# F4x1_Dev.net
KiCad netlist of a schematic drawn in Altium Designer
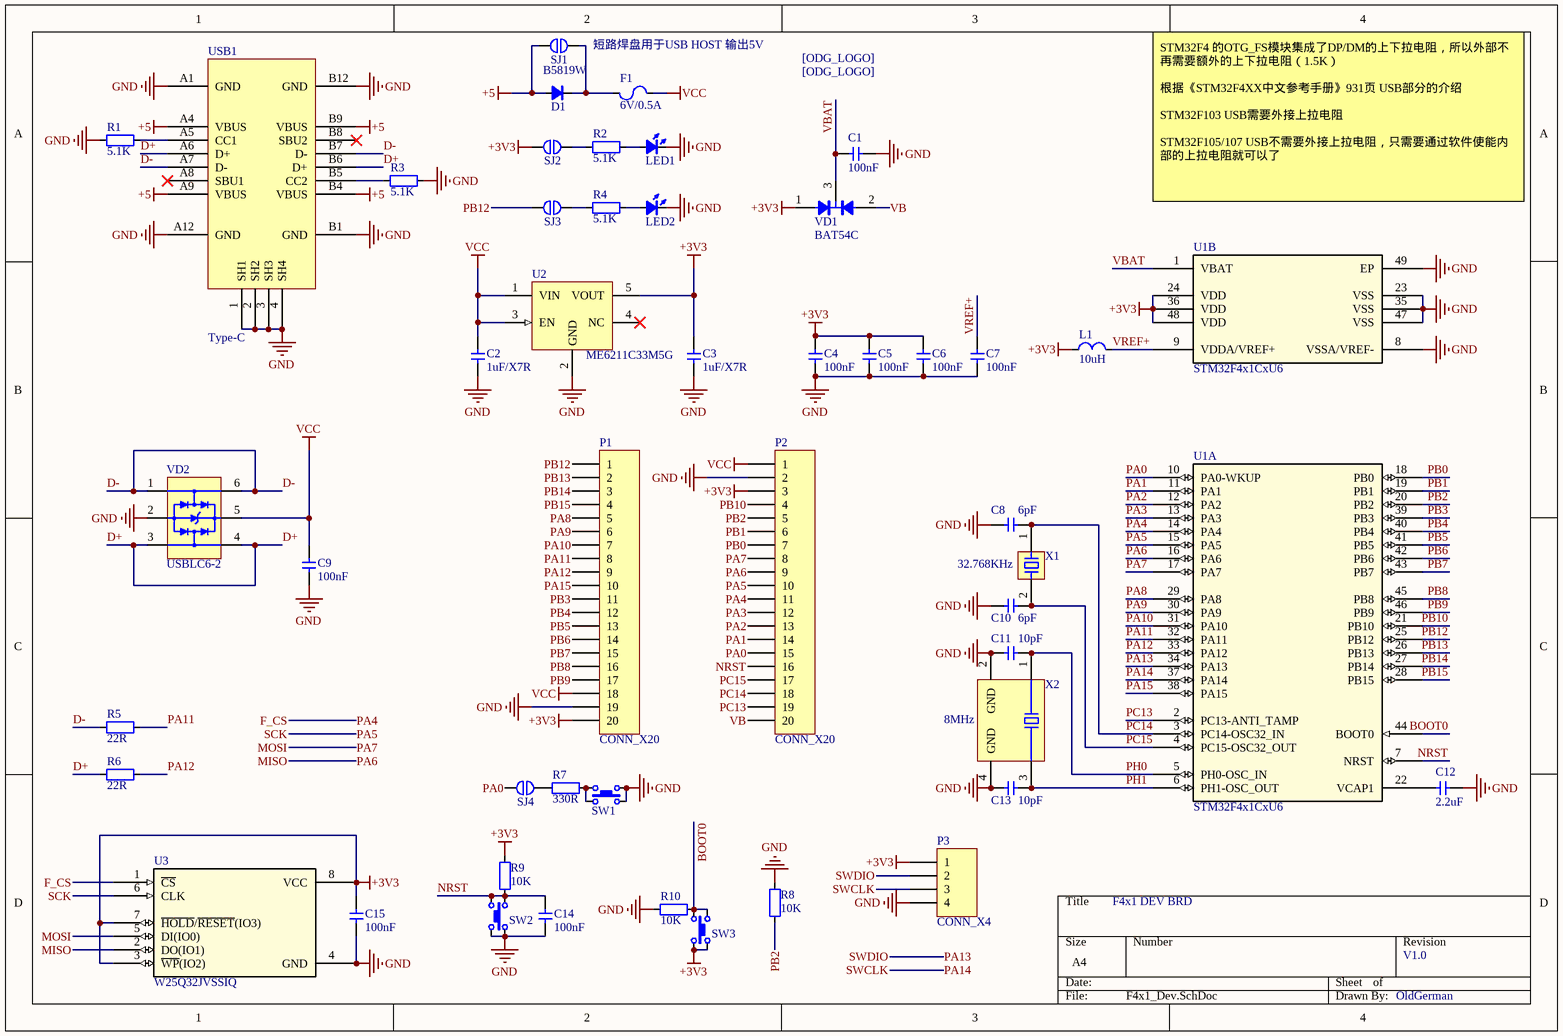
[diagram p0: F4x1_Dev.SchDoc]

(export (version "E")
  (design (tool "Eeschema 10.0.6"))
  (components
    (comp (ref "*1")
      (value "ODG_LOGO")
      (footprint "ODG_LOGO")
      (libsource (lib "ODG_AD_Lib") (part "ODG_LOGO"))
    )
    (comp (ref "*2")
      (value "ODG_LOGO")
      (footprint "ODG_LOGO")
      (libsource (lib "ODG_AD_Lib") (part "ODG_LOGO"))
    )
    (comp (ref "C1")
      (value "100nF")
      (footprint "C0603")
      (description "Capacitor")
      (libsource (lib "ODG_AD_Lib") (part "CAP"))
    )
    (comp (ref "C2")
      (value "1uF/X7R")
      (footprint "C0603")
      (description "Capacitor")
      (libsource (lib "ODG_AD_Lib") (part "CAP"))
    )
    (comp (ref "C3")
      (value "1uF/X7R")
      (footprint "C0603")
      (description "Capacitor")
      (libsource (lib "ODG_AD_Lib") (part "CAP"))
    )
    (comp (ref "C4")
      (value "100nF")
      (footprint "C0603")
      (description "Capacitor")
      (libsource (lib "ODG_AD_Lib") (part "CAP"))
    )
    (comp (ref "C5")
      (value "100nF")
      (footprint "C0603")
      (description "Capacitor")
      (libsource (lib "ODG_AD_Lib") (part "CAP"))
    )
    (comp (ref "C6")
      (value "100nF")
      (footprint "C0603")
      (description "Capacitor")
      (libsource (lib "ODG_AD_Lib") (part "CAP"))
    )
    (comp (ref "C7")
      (value "100nF")
      (footprint "C0603")
      (description "Capacitor")
      (libsource (lib "ODG_AD_Lib") (part "CAP"))
    )
    (comp (ref "C8")
      (value "6pF")
      (footprint "C0603")
      (description "Capacitor")
      (libsource (lib "ODG_AD_Lib") (part "CAP"))
    )
    (comp (ref "C9")
      (value "100nF")
      (footprint "C0603")
      (description "Capacitor")
      (libsource (lib "ODG_AD_Lib") (part "CAP"))
    )
    (comp (ref "C10")
      (value "6pF")
      (footprint "C0603")
      (description "Capacitor")
      (libsource (lib "ODG_AD_Lib") (part "CAP"))
    )
    (comp (ref "C11")
      (value "10pF")
      (footprint "C0603")
      (description "Capacitor")
      (libsource (lib "ODG_AD_Lib") (part "CAP"))
    )
    (comp (ref "C12")
      (value "2.2uF")
      (footprint "C0603")
      (description "Capacitor")
      (libsource (lib "ODG_AD_Lib") (part "CAP"))
    )
    (comp (ref "C13")
      (value "10pF")
      (footprint "C0603")
      (description "Capacitor")
      (libsource (lib "ODG_AD_Lib") (part "CAP"))
    )
    (comp (ref "C14")
      (value "100nF")
      (footprint "C0603")
      (description "Capacitor")
      (libsource (lib "ODG_AD_Lib") (part "CAP"))
    )
    (comp (ref "C15")
      (value "100nF")
      (footprint "C0603")
      (description "Capacitor")
      (libsource (lib "ODG_AD_Lib") (part "CAP"))
    )
    (comp (ref "D1")
      (value "B5819W")
      (footprint "SOD-323")
      (description "二极管")
      (libsource (lib "ODG_AD_Lib") (part "DIODE"))
    )
    (comp (ref "F1")
      (value "6V/0.5A")
      (footprint "FUSE0603_0.5MM")
      (description "贴片自恢复保险丝")
      (libsource (lib "ODG_AD_Lib") (part "FUSE"))
    )
    (comp (ref "L1")
      (value "10uH")
      (footprint "FER0603")
      (description "贴片叠层电感")
      (libsource (lib "ODG_AD_Lib") (part "inductor_mini"))
    )
    (comp (ref "LED1") (value "LED") (footprint "LED0603_GREEN") (libsource (lib "ODG_AD_Lib") (part "LED")))
    (comp (ref "LED2") (value "LED") (footprint "LED0603_YELLOW") (libsource (lib "ODG_AD_Lib") (part "LED")))
    (comp (ref "P1")
      (value "CONN_X20")
      (footprint "2.54MM_MALE_X20")
      (libsource (lib "ODG_AD_Lib") (part "CONN_X20"))
    )
    (comp (ref "P2")
      (value "CONN_X20")
      (footprint "2.54MM_MALE_X20")
      (libsource (lib "ODG_AD_Lib") (part "CONN_X20"))
    )
    (comp (ref "P3")
      (value "CONN_X4")
      (footprint "2.54mm_Male_x4")
      (libsource (lib "ODG_AD_Lib") (part "CONN_X4"))
    )
    (comp (ref "R1")
      (value "5.1K")
      (footprint "R0603")
      (description "Resistor")
      (libsource (lib "") (part "RES_1"))
    )
    (comp (ref "R2")
      (value "5.1K")
      (footprint "R0603")
      (description "Resistor")
      (libsource (lib "") (part "RES_1"))
    )
    (comp (ref "R3")
      (value "5.1K")
      (footprint "R0603")
      (description "Resistor")
      (libsource (lib "") (part "RES_1"))
    )
    (comp (ref "R4")
      (value "5.1K")
      (footprint "R0603")
      (description "Resistor")
      (libsource (lib "") (part "RES_1"))
    )
    (comp (ref "R5")
      (value "22R")
      (footprint "R0603")
      (description "Resistor")
      (libsource (lib "") (part "RES_1"))
    )
    (comp (ref "R6")
      (value "22R")
      (footprint "R0603")
      (description "Resistor")
      (libsource (lib "") (part "RES_1"))
    )
    (comp (ref "R7")
      (value "330R")
      (footprint "R0603")
      (description "Resistor")
      (libsource (lib "ODG_AD_Lib") (part "RES"))
    )
    (comp (ref "R8")
      (value "10K")
      (footprint "R0603")
      (description "Resistor")
      (libsource (lib "") (part "RES_2"))
    )
    (comp (ref "R9")
      (value "10K")
      (footprint "R0603")
      (description "Resistor")
      (libsource (lib "") (part "RES_3"))
    )
    (comp (ref "R10")
      (value "10K")
      (footprint "R0603")
      (description "Resistor")
      (libsource (lib "ODG_AD_Lib") (part "RES"))
    )
    (comp (ref "SJ1")
      (value "SJ_2P")
      (footprint "SJ_2P")
      (description "焊接跳线")
      (libsource (lib "ODG_AD_Lib") (part "SJ_2P"))
    )
    (comp (ref "SJ2")
      (value "SJ_2P")
      (footprint "SJ_2P_MINI")
      (description "焊接跳线")
      (libsource (lib "ODG_AD_Lib") (part "SJ_2P"))
    )
    (comp (ref "SJ3")
      (value "SJ_2P")
      (footprint "SJ_2P_MINI")
      (description "焊接跳线")
      (libsource (lib "ODG_AD_Lib") (part "SJ_2P"))
    )
    (comp (ref "SJ4")
      (value "SJ_2P")
      (footprint "SJ_2P_MINI")
      (description "焊接跳线")
      (libsource (lib "ODG_AD_Lib") (part "SJ_2P"))
    )
    (comp (ref "SW1")
      (value "Button-4P")
      (footprint "SWITCH_3X4X2.5_4PIN_SMD")
      (description "Button")
      (libsource (lib "ODG_AD_Lib") (part "Button-4P"))
    )
    (comp (ref "SW2")
      (value "Button-4P")
      (footprint "SWITCH_3X4X2.5_4PIN_SMD")
      (description "Button")
      (libsource (lib "ODG_AD_Lib") (part "Button-4P"))
    )
    (comp (ref "SW3")
      (value "Button-4P")
      (footprint "SWITCH_3X4X2.5_4PIN_SMD")
      (description "Button")
      (libsource (lib "ODG_AD_Lib") (part "Button-4P"))
    )
    (comp (ref "U1")
      (value "STM32F4x1CxU6")
      (footprint "UFQFPN-48_7X7X0P55MM_VIA")
      (description "No Description Available")
      (fields
        (field (name "MANUFACTURER_PART_NUMBER") "STM32F411CEU7")
        (field (name "COPYRIGHT") "Copyright (C) 2022 Ultra Librarian. All rights reserved.")
      )
      (libsource (lib "ODG_AD_Lib") (part "STM32F411CEU7"))
    )
    (comp (ref "U2")
      (value "ME6211C33M5G")
      (footprint "ANALOG TSOT-23-5 UJ-5")
      (description "线性稳压芯片")
      (fields (field (name "版权归属") "源创客"))
      (libsource (lib "ODG_AD_Lib") (part "ME6211C33M5G"))
    )
    (comp (ref "U3")
      (value "W25Q32JVSSIQ")
      (footprint "WIN_SS-8_WIN-L")
      (description "No Description Available")
      (fields
        (field (name "MANUFACTURER_PART_NUMBER") "W25Q16DVSSIG")
        (field (name "COPYRIGHT") "Copyright (C) 2022 Ultra Librarian. All rights reserved.")
      )
      (libsource (lib "ODG_AD_Lib") (part "W25Qxx"))
    )
    (comp (ref "USB1")
      (value "Type-C")
      (footprint "Type-C-TOP")
      (libsource (lib "ODG_AD_Lib") (part "USB-Type-C_16P"))
    )
    (comp (ref "VD1")
      (value "BAT54C")
      (footprint "ON SEMI SOT-23-3")
      (description "贴片肖特基二极管")
      (fields (field (name "版权归属") "源创客"))
      (libsource (lib "ODG_AD_Lib") (part "BAT54C"))
    )
    (comp (ref "VD2")
      (value "USBLC6-2")
      (footprint "MICROCHIP SOT-23-6 M6")
      (fields (field (name "版权归属") "源创客"))
      (libsource (lib "ODG_AD_Lib") (part "USBLC6-2"))
    )
    (comp (ref "X1")
      (value "32.768KHz")
      (footprint "XTAL_2P_3215")
      (description "2脚无源石英晶振")
      (fields (field (name "版权归属") "源创客"))
      (libsource (lib "ODG_AD_Lib") (part "XTAL-2P"))
    )
    (comp (ref "X2")
      (value "8MHz")
      (footprint "EPSON TSX-3225")
      (description "4脚无源石英晶振")
      (fields (field (name "版权归属") "源创客"))
      (libsource (lib "ODG_AD_Lib") (part "XTAL-4P"))
    )
  )
  (nets
    (net (code "1") (name "+3V3") (class "Default")
      (node (ref "C15") (pin "2") (pinfunction "2_2") (pintype "passive"))
      (node (ref "C3") (pin "2") (pinfunction "2_2") (pintype "passive"))
      (node (ref "C4") (pin "2") (pinfunction "2_2") (pintype "passive"))
      (node (ref "C5") (pin "1") (pinfunction "1_1") (pintype "passive"))
      (node (ref "C6") (pin "1") (pinfunction "1_1") (pintype "passive"))
      (node (ref "L1") (pin "1") (pinfunction "1_1") (pintype "passive"))
      (node (ref "P1") (pin "20") (pinfunction "20_20") (pintype "passive"))
      (node (ref "P2") (pin "3") (pinfunction "3_3") (pintype "passive"))
      (node (ref "P3") (pin "1") (pinfunction "1_1") (pintype "passive"))
      (node (ref "R9") (pin "1") (pinfunction "1_1") (pintype "passive"))
      (node (ref "SJ2") (pin "1") (pinfunction "1_1") (pintype "passive"))
      (node (ref "SW3") (pin "3") (pinfunction "3_3") (pintype "passive"))
      (node (ref "SW3") (pin "4") (pinfunction "4_4") (pintype "passive"))
      (node (ref "U1") (pin "24") (pinfunction "VDD_24") (pintype "power_in"))
      (node (ref "U1") (pin "36") (pinfunction "VDD_36") (pintype "power_in"))
      (node (ref "U1") (pin "48") (pinfunction "VDD_48") (pintype "power_in"))
      (node (ref "U2") (pin "5") (pinfunction "VOUT_5") (pintype "passive"))
      (node (ref "U3") (pin "3") (pinfunction "~{WP}(IO2)_3") (pintype "bidirectional"))
      (node (ref "U3") (pin "7") (pinfunction "~{HOLD}/~{RESET}(IO3)_7") (pintype "bidirectional"))
      (node (ref "U3") (pin "8") (pinfunction "VCC_8") (pintype "power_in"))
      (node (ref "VD1") (pin "1") (pinfunction "1_1") (pintype "passive"))
    )
    (net (code "2") (name "+5") (class "Default")
      (node (ref "D1") (pin "1") (pinfunction "A_1") (pintype "passive"))
      (node (ref "SJ1") (pin "1") (pinfunction "1_1") (pintype "passive"))
      (node (ref "USB1") (pin "A4") (pinfunction "VBUS_A4") (pintype "passive"))
      (node (ref "USB1") (pin "A9") (pinfunction "VBUS_A9") (pintype "passive"))
      (node (ref "USB1") (pin "B4") (pinfunction "VBUS_B4") (pintype "passive"))
      (node (ref "USB1") (pin "B9") (pinfunction "VBUS_B9") (pintype "passive"))
    )
    (net (code "3") (name "/BOOT0") (class "Default")
      (node (ref "R10") (pin "1") (pinfunction "1_1") (pintype "passive"))
      (node (ref "SW3") (pin "1") (pinfunction "1_1") (pintype "passive"))
      (node (ref "SW3") (pin "2") (pinfunction "2_2") (pintype "passive"))
      (node (ref "U1") (pin "44") (pinfunction "BOOT0_44") (pintype "input"))
    )
    (net (code "4") (name "/D+") (class "Default")
      (node (ref "R6") (pin "1") (pinfunction "1_1") (pintype "passive"))
      (node (ref "USB1") (pin "A6") (pinfunction "D+_A6") (pintype "passive"))
      (node (ref "USB1") (pin "B6") (pinfunction "D+_B6") (pintype "passive"))
      (node (ref "VD2") (pin "3") (pinfunction "I/O2_3") (pintype "passive"))
      (node (ref "VD2") (pin "4") (pinfunction "I/O2_4") (pintype "passive"))
    )
    (net (code "5") (name "/D-") (class "Default")
      (node (ref "R5") (pin "1") (pinfunction "1_1") (pintype "passive"))
      (node (ref "USB1") (pin "A7") (pinfunction "D-_A7") (pintype "passive"))
      (node (ref "USB1") (pin "B7") (pinfunction "D-_B7") (pintype "passive"))
      (node (ref "VD2") (pin "1") (pinfunction "I/O1_1") (pintype "passive"))
      (node (ref "VD2") (pin "6") (pinfunction "I/O1_6") (pintype "passive"))
    )
    (net (code "6") (name "/F_CS") (class "Default")
      (node (ref "P2") (pin "11") (pinfunction "11_11") (pintype "passive"))
      (node (ref "U1") (pin "14") (pinfunction "PA4_14") (pintype "bidirectional"))
      (node (ref "U3") (pin "1") (pinfunction "~{CS}_1") (pintype "input"))
    )
    (net (code "7") (name "/MISO") (class "Default")
      (node (ref "P2") (pin "9") (pinfunction "9_9") (pintype "passive"))
      (node (ref "U1") (pin "16") (pinfunction "PA6_16") (pintype "bidirectional"))
      (node (ref "U3") (pin "2") (pinfunction "DO(IO1)_2") (pintype "bidirectional"))
    )
    (net (code "8") (name "/MOSI") (class "Default")
      (node (ref "P2") (pin "8") (pinfunction "8_8") (pintype "passive"))
      (node (ref "U1") (pin "17") (pinfunction "PA7_17") (pintype "bidirectional"))
      (node (ref "U3") (pin "5") (pinfunction "DI(IO0)_5") (pintype "bidirectional"))
    )
    (net (code "9") (name "/NRST") (class "Default")
      (node (ref "C14") (pin "2") (pinfunction "2_2") (pintype "passive"))
      (node (ref "P2") (pin "16") (pinfunction "16_16") (pintype "passive"))
      (node (ref "R9") (pin "2") (pinfunction "2_2") (pintype "passive"))
      (node (ref "SW2") (pin "3") (pinfunction "3_3") (pintype "passive"))
      (node (ref "SW2") (pin "4") (pinfunction "4_4") (pintype "passive"))
      (node (ref "U1") (pin "7") (pinfunction "NRST_7") (pintype "bidirectional"))
    )
    (net (code "10") (name "/PA0") (class "Default")
      (node (ref "P2") (pin "15") (pinfunction "15_15") (pintype "passive"))
      (node (ref "SJ4") (pin "1") (pinfunction "1_1") (pintype "passive"))
      (node (ref "U1") (pin "10") (pinfunction "PA0-WKUP_10") (pintype "bidirectional"))
    )
    (net (code "11") (name "/PA1") (class "Default")
      (node (ref "P2") (pin "14") (pinfunction "14_14") (pintype "passive"))
      (node (ref "U1") (pin "11") (pinfunction "PA1_11") (pintype "bidirectional"))
    )
    (net (code "12") (name "/PA2") (class "Default")
      (node (ref "P2") (pin "13") (pinfunction "13_13") (pintype "passive"))
      (node (ref "U1") (pin "12") (pinfunction "PA2_12") (pintype "bidirectional"))
    )
    (net (code "13") (name "/PA3") (class "Default")
      (node (ref "P2") (pin "12") (pinfunction "12_12") (pintype "passive"))
      (node (ref "U1") (pin "13") (pinfunction "PA3_13") (pintype "bidirectional"))
    )
    (net (code "14") (name "/PA5") (class "Default")
      (node (ref "P2") (pin "10") (pinfunction "10_10") (pintype "passive"))
      (node (ref "U1") (pin "15") (pinfunction "PA5_15") (pintype "bidirectional"))
      (node (ref "U3") (pin "6") (pinfunction "CLK_6") (pintype "input"))
    )
    (net (code "15") (name "/PA8") (class "Default")
      (node (ref "P1") (pin "5") (pinfunction "5_5") (pintype "passive"))
      (node (ref "U1") (pin "29") (pinfunction "PA8_29") (pintype "bidirectional"))
    )
    (net (code "16") (name "/PA9") (class "Default")
      (node (ref "P1") (pin "6") (pinfunction "6_6") (pintype "passive"))
      (node (ref "U1") (pin "30") (pinfunction "PA9_30") (pintype "bidirectional"))
    )
    (net (code "17") (name "/PA10") (class "Default")
      (node (ref "P1") (pin "7") (pinfunction "7_7") (pintype "passive"))
      (node (ref "U1") (pin "31") (pinfunction "PA10_31") (pintype "bidirectional"))
    )
    (net (code "18") (name "/PA11") (class "Default")
      (node (ref "P1") (pin "8") (pinfunction "8_8") (pintype "passive"))
      (node (ref "R5") (pin "2") (pinfunction "2_2") (pintype "passive"))
      (node (ref "U1") (pin "32") (pinfunction "PA11_32") (pintype "bidirectional"))
    )
    (net (code "19") (name "/PA12") (class "Default")
      (node (ref "P1") (pin "9") (pinfunction "9_9") (pintype "passive"))
      (node (ref "R6") (pin "2") (pinfunction "2_2") (pintype "passive"))
      (node (ref "U1") (pin "33") (pinfunction "PA12_33") (pintype "bidirectional"))
    )
    (net (code "20") (name "/PA13") (class "Default")
      (node (ref "P3") (pin "2") (pinfunction "2_2") (pintype "passive"))
      (node (ref "U1") (pin "34") (pinfunction "PA13_34") (pintype "bidirectional"))
    )
    (net (code "21") (name "/PA14") (class "Default")
      (node (ref "P3") (pin "3") (pinfunction "3_3") (pintype "passive"))
      (node (ref "U1") (pin "37") (pinfunction "PA14_37") (pintype "bidirectional"))
    )
    (net (code "22") (name "/PA15") (class "Default")
      (node (ref "P1") (pin "10") (pinfunction "10_10") (pintype "passive"))
      (node (ref "U1") (pin "38") (pinfunction "PA15_38") (pintype "bidirectional"))
    )
    (net (code "23") (name "/PB0") (class "Default")
      (node (ref "P2") (pin "7") (pinfunction "7_7") (pintype "passive"))
      (node (ref "U1") (pin "18") (pinfunction "PB0_18") (pintype "bidirectional"))
    )
    (net (code "24") (name "/PB1") (class "Default")
      (node (ref "P2") (pin "6") (pinfunction "6_6") (pintype "passive"))
      (node (ref "U1") (pin "19") (pinfunction "PB1_19") (pintype "bidirectional"))
    )
    (net (code "25") (name "/PB2") (class "Default")
      (node (ref "P2") (pin "5") (pinfunction "5_5") (pintype "passive"))
      (node (ref "R8") (pin "1") (pinfunction "1_1") (pintype "passive"))
      (node (ref "U1") (pin "20") (pinfunction "PB2_20") (pintype "bidirectional"))
    )
    (net (code "26") (name "/PB3") (class "Default")
      (node (ref "P1") (pin "11") (pinfunction "11_11") (pintype "passive"))
      (node (ref "U1") (pin "39") (pinfunction "PB3_39") (pintype "bidirectional"))
    )
    (net (code "27") (name "/PB4") (class "Default")
      (node (ref "P1") (pin "12") (pinfunction "12_12") (pintype "passive"))
      (node (ref "U1") (pin "40") (pinfunction "PB4_40") (pintype "bidirectional"))
    )
    (net (code "28") (name "/PB5") (class "Default")
      (node (ref "P1") (pin "13") (pinfunction "13_13") (pintype "passive"))
      (node (ref "U1") (pin "41") (pinfunction "PB5_41") (pintype "bidirectional"))
    )
    (net (code "29") (name "/PB6") (class "Default")
      (node (ref "P1") (pin "14") (pinfunction "14_14") (pintype "passive"))
      (node (ref "U1") (pin "42") (pinfunction "PB6_42") (pintype "bidirectional"))
    )
    (net (code "30") (name "/PB7") (class "Default")
      (node (ref "P1") (pin "15") (pinfunction "15_15") (pintype "passive"))
      (node (ref "U1") (pin "43") (pinfunction "PB7_43") (pintype "bidirectional"))
    )
    (net (code "31") (name "/PB8") (class "Default")
      (node (ref "P1") (pin "16") (pinfunction "16_16") (pintype "passive"))
      (node (ref "U1") (pin "45") (pinfunction "PB8_45") (pintype "bidirectional"))
    )
    (net (code "32") (name "/PB9") (class "Default")
      (node (ref "P1") (pin "17") (pinfunction "17_17") (pintype "passive"))
      (node (ref "U1") (pin "46") (pinfunction "PB9_46") (pintype "bidirectional"))
    )
    (net (code "33") (name "/PB10") (class "Default")
      (node (ref "P2") (pin "4") (pinfunction "4_4") (pintype "passive"))
      (node (ref "U1") (pin "21") (pinfunction "PB10_21") (pintype "bidirectional"))
    )
    (net (code "34") (name "/PB12") (class "Default")
      (node (ref "P1") (pin "1") (pinfunction "1_1") (pintype "passive"))
      (node (ref "SJ3") (pin "1") (pinfunction "1_1") (pintype "passive"))
      (node (ref "U1") (pin "25") (pinfunction "PB12_25") (pintype "bidirectional"))
    )
    (net (code "35") (name "/PB13") (class "Default")
      (node (ref "P1") (pin "2") (pinfunction "2_2") (pintype "passive"))
      (node (ref "U1") (pin "26") (pinfunction "PB13_26") (pintype "bidirectional"))
    )
    (net (code "36") (name "/PB14") (class "Default")
      (node (ref "P1") (pin "3") (pinfunction "3_3") (pintype "passive"))
      (node (ref "U1") (pin "27") (pinfunction "PB14_27") (pintype "bidirectional"))
    )
    (net (code "37") (name "/PB15") (class "Default")
      (node (ref "P1") (pin "4") (pinfunction "4_4") (pintype "passive"))
      (node (ref "U1") (pin "28") (pinfunction "PB15_28") (pintype "bidirectional"))
    )
    (net (code "38") (name "/PC13") (class "Default")
      (node (ref "P2") (pin "19") (pinfunction "19_19") (pintype "passive"))
      (node (ref "U1") (pin "2") (pinfunction "PC13-ANTI_TAMP_2") (pintype "bidirectional"))
    )
    (net (code "39") (name "/PC14") (class "Default")
      (node (ref "C8") (pin "1") (pinfunction "1_1") (pintype "passive"))
      (node (ref "P2") (pin "18") (pinfunction "18_18") (pintype "passive"))
      (node (ref "U1") (pin "3") (pinfunction "PC14-OSC32_IN_3") (pintype "bidirectional"))
      (node (ref "X1") (pin "1") (pinfunction "1_1") (pintype "passive"))
    )
    (net (code "40") (name "/PC15") (class "Default")
      (node (ref "C10") (pin "1") (pinfunction "1_1") (pintype "passive"))
      (node (ref "P2") (pin "17") (pinfunction "17_17") (pintype "passive"))
      (node (ref "U1") (pin "4") (pinfunction "PC15-OSC32_OUT_4") (pintype "bidirectional"))
      (node (ref "X1") (pin "2") (pinfunction "2_2") (pintype "passive"))
    )
    (net (code "41") (name "/PH0") (class "Default")
      (node (ref "C11") (pin "1") (pinfunction "1_1") (pintype "passive"))
      (node (ref "U1") (pin "5") (pinfunction "PH0-OSC_IN_5") (pintype "bidirectional"))
      (node (ref "X2") (pin "1") (pinfunction "1_1") (pintype "passive"))
    )
    (net (code "42") (name "/PH1") (class "Default")
      (node (ref "C13") (pin "1") (pinfunction "1_1") (pintype "passive"))
      (node (ref "U1") (pin "6") (pinfunction "PH1-OSC_OUT_6") (pintype "bidirectional"))
      (node (ref "X2") (pin "3") (pinfunction "3_3") (pintype "passive"))
    )
    (net (code "43") (name "/VB") (class "Default")
      (node (ref "P2") (pin "20") (pinfunction "20_20") (pintype "passive"))
      (node (ref "VD1") (pin "2") (pinfunction "2_2") (pintype "passive"))
    )
    (net (code "44") (name "/VBAT") (class "Default")
      (node (ref "C1") (pin "1") (pinfunction "1_1") (pintype "passive"))
      (node (ref "U1") (pin "1") (pinfunction "VBAT_1") (pintype "power_in"))
      (node (ref "VD1") (pin "3") (pinfunction "3_3") (pintype "passive"))
    )
    (net (code "45") (name "/VREF+") (class "Default")
      (node (ref "C7") (pin "2") (pinfunction "2_2") (pintype "passive"))
      (node (ref "L1") (pin "2") (pinfunction "2_2") (pintype "passive"))
      (node (ref "U1") (pin "9") (pinfunction "VDDA/VREF+_9") (pintype "power_in"))
    )
    (net (code "46") (name "GND") (class "Default")
      (node (ref "C1") (pin "2") (pinfunction "2_2") (pintype "passive"))
      (node (ref "C10") (pin "2") (pinfunction "2_2") (pintype "passive"))
      (node (ref "C11") (pin "2") (pinfunction "2_2") (pintype "passive"))
      (node (ref "C12") (pin "1") (pinfunction "1_1") (pintype "passive"))
      (node (ref "C13") (pin "2") (pinfunction "2_2") (pintype "passive"))
      (node (ref "C14") (pin "1") (pinfunction "1_1") (pintype "passive"))
      (node (ref "C15") (pin "1") (pinfunction "1_1") (pintype "passive"))
      (node (ref "C2") (pin "1") (pinfunction "1_1") (pintype "passive"))
      (node (ref "C3") (pin "1") (pinfunction "1_1") (pintype "passive"))
      (node (ref "C4") (pin "1") (pinfunction "1_1") (pintype "passive"))
      (node (ref "C5") (pin "2") (pinfunction "2_2") (pintype "passive"))
      (node (ref "C6") (pin "2") (pinfunction "2_2") (pintype "passive"))
      (node (ref "C7") (pin "1") (pinfunction "1_1") (pintype "passive"))
      (node (ref "C8") (pin "2") (pinfunction "2_2") (pintype "passive"))
      (node (ref "C9") (pin "1") (pinfunction "1_1") (pintype "passive"))
      (node (ref "LED1") (pin "2") (pinfunction "K_2") (pintype "passive"))
      (node (ref "LED2") (pin "2") (pinfunction "K_2") (pintype "passive"))
      (node (ref "P1") (pin "19") (pinfunction "19_19") (pintype "passive"))
      (node (ref "P2") (pin "2") (pinfunction "2_2") (pintype "passive"))
      (node (ref "P3") (pin "4") (pinfunction "4_4") (pintype "passive"))
      (node (ref "R1") (pin "1") (pinfunction "1_1") (pintype "passive"))
      (node (ref "R10") (pin "2") (pinfunction "2_2") (pintype "passive"))
      (node (ref "R3") (pin "2") (pinfunction "2_2") (pintype "passive"))
      (node (ref "R8") (pin "2") (pinfunction "2_2") (pintype "passive"))
      (node (ref "SW1") (pin "3") (pinfunction "3_3") (pintype "passive"))
      (node (ref "SW1") (pin "4") (pinfunction "4_4") (pintype "passive"))
      (node (ref "SW2") (pin "1") (pinfunction "1_1") (pintype "passive"))
      (node (ref "SW2") (pin "2") (pinfunction "2_2") (pintype "passive"))
      (node (ref "U1") (pin "23") (pinfunction "VSS_23") (pintype "power_in"))
      (node (ref "U1") (pin "35") (pinfunction "VSS_35") (pintype "power_in"))
      (node (ref "U1") (pin "47") (pinfunction "VSS_47") (pintype "power_in"))
      (node (ref "U1") (pin "49") (pinfunction "EP_49") (pintype "passive"))
      (node (ref "U1") (pin "8") (pinfunction "VSSA/VREF-_8") (pintype "power_in"))
      (node (ref "U2") (pin "2") (pinfunction "GND_2") (pintype "passive"))
      (node (ref "U3") (pin "4") (pinfunction "GND_4") (pintype "power_in"))
      (node (ref "USB1") (pin "1") (pinfunction "SH1_1") (pintype "passive"))
      (node (ref "USB1") (pin "2") (pinfunction "SH2_2") (pintype "passive"))
      (node (ref "USB1") (pin "3") (pinfunction "SH3_3") (pintype "passive"))
      (node (ref "USB1") (pin "4") (pinfunction "SH4_4") (pintype "passive"))
      (node (ref "USB1") (pin "A1") (pinfunction "GND_A1") (pintype "passive"))
      (node (ref "USB1") (pin "A12") (pinfunction "GND_A12") (pintype "passive"))
      (node (ref "USB1") (pin "B1") (pinfunction "GND_B1") (pintype "passive"))
      (node (ref "USB1") (pin "B12") (pinfunction "GND_B12") (pintype "passive"))
      (node (ref "VD2") (pin "2") (pinfunction "GND_2") (pintype "passive"))
      (node (ref "X2") (pin "2") (pinfunction "GND_2") (pintype "passive"))
      (node (ref "X2") (pin "4") (pinfunction "GND_4") (pintype "passive"))
    )
    (net (code "47") (name "Net-(D1-C)") (class "Default")
      (node (ref "D1") (pin "2") (pinfunction "C_2") (pintype "passive"))
      (node (ref "F1") (pin "1") (pinfunction "1_1") (pintype "passive"))
      (node (ref "SJ1") (pin "2") (pinfunction "2_2") (pintype "passive"))
    )
    (net (code "48") (name "Net-(LED1-A)") (class "Default")
      (node (ref "LED1") (pin "1") (pinfunction "A_1") (pintype "passive"))
      (node (ref "R2") (pin "2") (pinfunction "2_2") (pintype "passive"))
    )
    (net (code "49") (name "Net-(LED2-A)") (class "Default")
      (node (ref "LED2") (pin "1") (pinfunction "A_1") (pintype "passive"))
      (node (ref "R4") (pin "2") (pinfunction "2_2") (pintype "passive"))
    )
    (net (code "50") (name "Net-(R2-Pad1)") (class "Default")
      (node (ref "R2") (pin "1") (pinfunction "1_1") (pintype "passive"))
      (node (ref "SJ2") (pin "2") (pinfunction "2_2") (pintype "passive"))
    )
    (net (code "51") (name "Net-(R4-Pad1)") (class "Default")
      (node (ref "R4") (pin "1") (pinfunction "1_1") (pintype "passive"))
      (node (ref "SJ3") (pin "2") (pinfunction "2_2") (pintype "passive"))
    )
    (net (code "52") (name "Net-(R7-Pad1)") (class "Default")
      (node (ref "R7") (pin "1") (pinfunction "1_1") (pintype "passive"))
      (node (ref "SW1") (pin "1") (pinfunction "1_1") (pintype "passive"))
      (node (ref "SW1") (pin "2") (pinfunction "2_2") (pintype "passive"))
    )
    (net (code "53") (name "Net-(R7-Pad2)") (class "Default")
      (node (ref "R7") (pin "2") (pinfunction "2_2") (pintype "passive"))
      (node (ref "SJ4") (pin "2") (pinfunction "2_2") (pintype "passive"))
    )
    (net (code "54") (name "Net-(U1A-VCAP1)") (class "Default")
      (node (ref "C12") (pin "2") (pinfunction "2_2") (pintype "passive"))
      (node (ref "U1") (pin "22") (pinfunction "VCAP1_22") (pintype "power_in"))
    )
    (net (code "55") (name "Net-(USB1-CC1)") (class "Default")
      (node (ref "R1") (pin "2") (pinfunction "2_2") (pintype "passive"))
      (node (ref "USB1") (pin "A5") (pinfunction "CC1_A5") (pintype "passive"))
    )
    (net (code "56") (name "Net-(USB1-CC2)") (class "Default")
      (node (ref "R3") (pin "1") (pinfunction "1_1") (pintype "passive"))
      (node (ref "USB1") (pin "B5") (pinfunction "CC2_B5") (pintype "passive"))
    )
    (net (code "57") (name "VCC") (class "Default")
      (node (ref "C2") (pin "2") (pinfunction "2_2") (pintype "passive"))
      (node (ref "C9") (pin "2") (pinfunction "2_2") (pintype "passive"))
      (node (ref "F1") (pin "2") (pinfunction "2_2") (pintype "passive"))
      (node (ref "P1") (pin "18") (pinfunction "18_18") (pintype "passive"))
      (node (ref "P2") (pin "1") (pinfunction "1_1") (pintype "passive"))
      (node (ref "U2") (pin "1") (pinfunction "VIN_1") (pintype "passive"))
      (node (ref "U2") (pin "3") (pinfunction "EN_3") (pintype "input"))
      (node (ref "VD2") (pin "5") (pinfunction "VBUS_5") (pintype "passive"))
    )
    (net (code "58") (name "unconnected-(U2-NC-Pad4)") (class "Default")
      (node (ref "U2") (pin "4") (pinfunction "NC_4") (pintype "passive+no_connect"))
    )
    (net (code "59") (name "unconnected-(USB1-SBU1-PadA8)") (class "Default")
      (node (ref "USB1") (pin "A8") (pinfunction "SBU1_A8") (pintype "passive+no_connect"))
    )
    (net (code "60") (name "unconnected-(USB1-SBU2-PadB8)") (class "Default")
      (node (ref "USB1") (pin "B8") (pinfunction "SBU2_B8") (pintype "passive+no_connect"))
    )
  )
)
